# vcnl4000.net
KiCad netlist of a schematic drawn in EAGLE
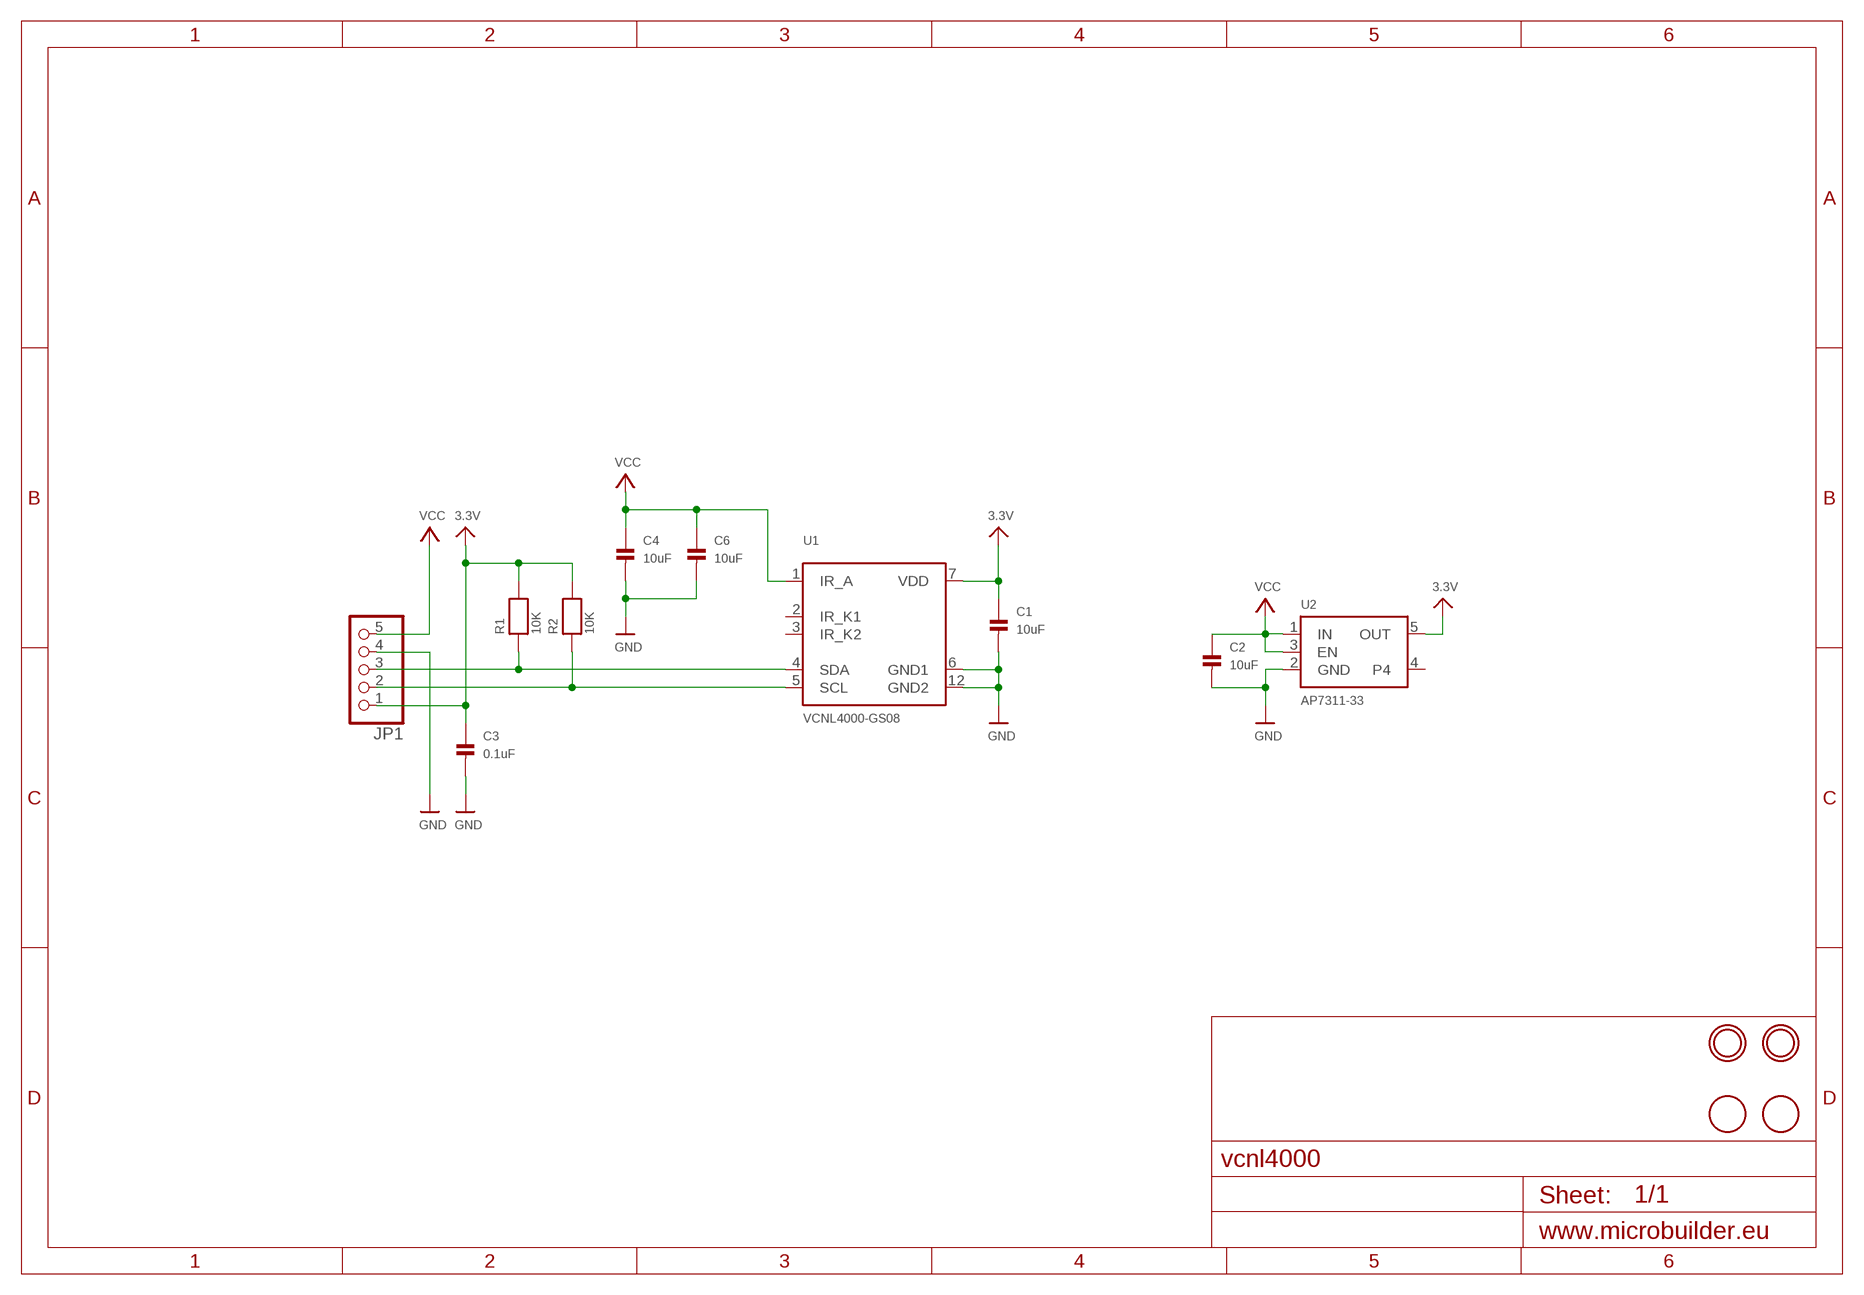
[diagram p0: schematic, sheet 1]

(export (version "E")
  (design (tool "Eeschema 10.0.6"))
  (components
    (comp (ref "C1")
      (value "10uF")
      (footprint "eagle-import:0805")
      (libsource (lib "eagle-import") (part "CAP_CERAMIC0805"))
    )
    (comp (ref "C2")
      (value "10uF")
      (footprint "eagle-import:0805")
      (libsource (lib "eagle-import") (part "CAP_CERAMIC0805"))
    )
    (comp (ref "C3")
      (value "0.1uF")
      (footprint "eagle-import:0805")
      (libsource (lib "eagle-import") (part "CAP_CERAMIC0805"))
    )
    (comp (ref "C4")
      (value "10uF")
      (footprint "eagle-import:0805")
      (libsource (lib "eagle-import") (part "CAP_CERAMIC0805"))
    )
    (comp (ref "C6")
      (value "10uF")
      (footprint "eagle-import:0805")
      (libsource (lib "eagle-import") (part "CAP_CERAMIC0805"))
    )
    (comp (ref "JP1")
      (value "HEADER-1X576MIL")
      (footprint "eagle-import:1X05_ROUND_76")
      (libsource (lib "eagle-import") (part "HEADER-1X576MIL"))
    )
    (comp (ref "R1")
      (value "10K")
      (footprint "eagle-import:0805")
      (libsource (lib "eagle-import") (part "RESISTOR0805"))
    )
    (comp (ref "R2")
      (value "10K")
      (footprint "eagle-import:0805")
      (libsource (lib "eagle-import") (part "RESISTOR0805"))
    )
    (comp (ref "U$5")
      (value "MOUNTINGHOLE2.0")
      (footprint "eagle-import:MOUNTINGHOLE_2.0_PLATED")
      (libsource (lib "eagle-import") (part "MOUNTINGHOLE2.0"))
    )
    (comp (ref "U$6")
      (value "MOUNTINGHOLE2.0")
      (footprint "eagle-import:MOUNTINGHOLE_2.0_PLATED")
      (libsource (lib "eagle-import") (part "MOUNTINGHOLE2.0"))
    )
    (comp (ref "U$7")
      (value "FIDUCIAL")
      (footprint "eagle-import:FIDUCIAL_1MM")
      (libsource (lib "eagle-import") (part "FIDUCIAL"))
    )
    (comp (ref "U$8")
      (value "FIDUCIAL")
      (footprint "eagle-import:FIDUCIAL_1MM")
      (libsource (lib "eagle-import") (part "FIDUCIAL"))
    )
    (comp (ref "U1")
      (value "VCNL4000-GS08")
      (footprint "eagle-import:VCNL4000")
      (libsource (lib "eagle-import") (part "VCNL4000"))
    )
    (comp (ref "U2")
      (value "AP7311-33")
      (footprint "eagle-import:SOT23-5")
      (libsource (lib "eagle-import") (part "VREG_SOT23-5"))
    )
  )
  (nets
    (net (code "1") (name "3.3V") (class "Default")
      (node (ref "C1") (pin "1") (pinfunction "P$1_1") (pintype "passive"))
      (node (ref "C3") (pin "1") (pinfunction "P$1_1") (pintype "passive"))
      (node (ref "JP1") (pin "1") (pinfunction "1_1") (pintype "passive"))
      (node (ref "R1") (pin "2") (pinfunction "2_2") (pintype "passive"))
      (node (ref "R2") (pin "2") (pinfunction "2_2") (pintype "passive"))
      (node (ref "U1") (pin "7") (pinfunction "VDD_7") (pintype "bidirectional"))
      (node (ref "U2") (pin "5") (pinfunction "OUT_5") (pintype "bidirectional"))
    )
    (net (code "2") (name "GND") (class "Default")
      (node (ref "C1") (pin "2") (pinfunction "P$2_2") (pintype "passive"))
      (node (ref "C2") (pin "2") (pinfunction "P$2_2") (pintype "passive"))
      (node (ref "C3") (pin "2") (pinfunction "P$2_2") (pintype "passive"))
      (node (ref "C4") (pin "2") (pinfunction "P$2_2") (pintype "passive"))
      (node (ref "C6") (pin "2") (pinfunction "P$2_2") (pintype "passive"))
      (node (ref "JP1") (pin "4") (pinfunction "4_4") (pintype "passive"))
      (node (ref "U1") (pin "12") (pinfunction "GND2_12") (pintype "bidirectional"))
      (node (ref "U1") (pin "6") (pinfunction "GND1_6") (pintype "bidirectional"))
      (node (ref "U2") (pin "2") (pinfunction "GND_2") (pintype "bidirectional"))
    )
    (net (code "3") (name "Net-(U1-SCL)") (class "Default")
      (node (ref "JP1") (pin "2") (pinfunction "2_2") (pintype "passive"))
      (node (ref "R2") (pin "1") (pinfunction "1_1") (pintype "passive"))
      (node (ref "U1") (pin "5") (pinfunction "SCL_5") (pintype "bidirectional"))
    )
    (net (code "4") (name "Net-(U1-SDA)") (class "Default")
      (node (ref "JP1") (pin "3") (pinfunction "3_3") (pintype "passive"))
      (node (ref "R1") (pin "1") (pinfunction "1_1") (pintype "passive"))
      (node (ref "U1") (pin "4") (pinfunction "SDA_4") (pintype "bidirectional"))
    )
    (net (code "5") (name "VCC") (class "Default")
      (node (ref "C2") (pin "1") (pinfunction "P$1_1") (pintype "passive"))
      (node (ref "C4") (pin "1") (pinfunction "P$1_1") (pintype "passive"))
      (node (ref "C6") (pin "1") (pinfunction "P$1_1") (pintype "passive"))
      (node (ref "JP1") (pin "5") (pinfunction "5_5") (pintype "passive"))
      (node (ref "U1") (pin "1") (pinfunction "IR_A_1") (pintype "bidirectional"))
      (node (ref "U2") (pin "1") (pinfunction "IN_1") (pintype "bidirectional"))
      (node (ref "U2") (pin "3") (pinfunction "EN_3") (pintype "bidirectional"))
    )
    (net (code "6") (name "unconnected-(U1-IR_K1-Pad2)") (class "Default")
      (node (ref "U1") (pin "2") (pinfunction "IR_K1_2") (pintype "bidirectional"))
    )
    (net (code "7") (name "unconnected-(U1-IR_K2-Pad3)") (class "Default")
      (node (ref "U1") (pin "3") (pinfunction "IR_K2_3") (pintype "bidirectional"))
    )
    (net (code "8") (name "unconnected-(U2-P4-Pad4)") (class "Default")
      (node (ref "U2") (pin "4") (pinfunction "P4_4") (pintype "bidirectional"))
    )
  )
)
